# Power_18.net
KiCad netlist of a schematic drawn in Altium Designer
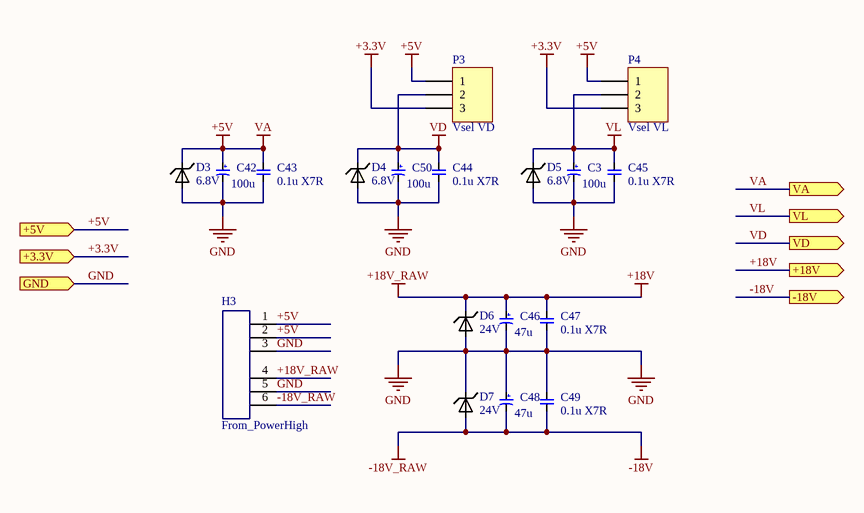
[diagram p0: Power_18.SchDoc]

(export (version "E")
  (design (tool "Eeschema 10.0.6"))
  (components
    (comp (ref "C3")
      (value "100u")
      (footprint "cap 4x5.4")
      (libsource (lib "Codec_board") (part "Cap_electrolytic"))
    )
    (comp (ref "C42")
      (value "100u")
      (footprint "cap 4x5.4")
      (libsource (lib "Codec_board") (part "Cap_electrolytic"))
    )
    (comp (ref "C43") (value "0.1u X7R") (footprint "0805_cap") (libsource (lib "Codec_board") (part "Cap")))
    (comp (ref "C44") (value "0.1u X7R") (footprint "0805_cap") (libsource (lib "Codec_board") (part "Cap")))
    (comp (ref "C45") (value "0.1u X7R") (footprint "0805_cap") (libsource (lib "Codec_board") (part "Cap")))
    (comp (ref "C46")
      (value "47u")
      (footprint "cap 4x5.4")
      (libsource (lib "Codec_board") (part "Cap_electrolytic"))
    )
    (comp (ref "C47") (value "0.1u X7R") (footprint "0805_cap") (libsource (lib "Codec_board") (part "Cap")))
    (comp (ref "C48")
      (value "47u")
      (footprint "cap 4x5.4")
      (libsource (lib "Codec_board") (part "Cap_electrolytic"))
    )
    (comp (ref "C49") (value "0.1u X7R") (footprint "0805_cap") (libsource (lib "Codec_board") (part "Cap")))
    (comp (ref "C50")
      (value "100u")
      (footprint "cap 4x5.4")
      (libsource (lib "Codec_board") (part "Cap_electrolytic"))
    )
    (comp (ref "D3") (value "6.8V") (footprint "SOD-80") (libsource (lib "Codec_board") (part "Stabilitron")))
    (comp (ref "D4") (value "6.8V") (footprint "SOD-80") (libsource (lib "Codec_board") (part "Stabilitron")))
    (comp (ref "D5") (value "6.8V") (footprint "SOD-80") (libsource (lib "Codec_board") (part "Stabilitron")))
    (comp (ref "D6") (value "24V") (footprint "SOD-80") (libsource (lib "Codec_board") (part "Stabilitron")))
    (comp (ref "D7") (value "24V") (footprint "SOD-80") (libsource (lib "Codec_board") (part "Stabilitron")))
    (comp (ref "H3")
      (value "From_PowerHigh")
      (footprint "header-6_male")
      (libsource (lib "Codec_board") (part "arduino_header_6"))
    )
    (comp (ref "P3")
      (value "Vsel VD")
      (footprint "HDR1X3")
      (description "Header, 3-Pin")
      (fields (field (name "PUBLISHER") "Altium Limited"))
      (libsource (lib "Miscellaneous Connectors") (part "Header 3"))
    )
    (comp (ref "P4")
      (value "Vsel VL")
      (footprint "HDR1X3")
      (description "Header, 3-Pin")
      (fields (field (name "PUBLISHER") "Altium Limited"))
      (libsource (lib "Miscellaneous Connectors") (part "Header 3"))
    )
  )
  (nets
    (net (code "1") (name "+3.3V") (class "Default")
      (node (ref "P3") (pin "3") (pinfunction "3_3") (pintype "passive"))
      (node (ref "P4") (pin "3") (pinfunction "3_3") (pintype "passive"))
    )
    (net (code "2") (name "+5V") (class "Default")
      (node (ref "C42") (pin "1") (pinfunction "1_1") (pintype "passive"))
      (node (ref "C43") (pin "2") (pinfunction "2_2") (pintype "passive"))
      (node (ref "D3") (pin "C") (pinfunction "C_C") (pintype "passive"))
      (node (ref "H3") (pin "1") (pinfunction "1_1") (pintype "passive"))
      (node (ref "H3") (pin "2") (pinfunction "2_2") (pintype "passive"))
      (node (ref "P3") (pin "1") (pinfunction "1_1") (pintype "passive"))
      (node (ref "P4") (pin "1") (pinfunction "1_1") (pintype "passive"))
    )
    (net (code "3") (name "+18V") (class "Default")
      (node (ref "C46") (pin "1") (pinfunction "1_1") (pintype "passive"))
      (node (ref "C47") (pin "2") (pinfunction "2_2") (pintype "passive"))
      (node (ref "D6") (pin "C") (pinfunction "C_C") (pintype "passive"))
      (node (ref "H3") (pin "4") (pinfunction "4_4") (pintype "passive"))
    )
    (net (code "4") (name "-18V") (class "Default")
      (node (ref "C48") (pin "2") (pinfunction "2_2") (pintype "passive"))
      (node (ref "C49") (pin "1") (pinfunction "1_1") (pintype "passive"))
      (node (ref "D7") (pin "A") (pinfunction "A_A") (pintype "passive"))
      (node (ref "H3") (pin "6") (pinfunction "6_6") (pintype "passive"))
    )
    (net (code "5") (name "GND") (class "Default")
      (node (ref "C3") (pin "2") (pinfunction "2_2") (pintype "passive"))
      (node (ref "C42") (pin "2") (pinfunction "2_2") (pintype "passive"))
      (node (ref "C43") (pin "1") (pinfunction "1_1") (pintype "passive"))
      (node (ref "C44") (pin "1") (pinfunction "1_1") (pintype "passive"))
      (node (ref "C45") (pin "1") (pinfunction "1_1") (pintype "passive"))
      (node (ref "C46") (pin "2") (pinfunction "2_2") (pintype "passive"))
      (node (ref "C47") (pin "1") (pinfunction "1_1") (pintype "passive"))
      (node (ref "C48") (pin "1") (pinfunction "1_1") (pintype "passive"))
      (node (ref "C49") (pin "2") (pinfunction "2_2") (pintype "passive"))
      (node (ref "C50") (pin "2") (pinfunction "2_2") (pintype "passive"))
      (node (ref "D3") (pin "A") (pinfunction "A_A") (pintype "passive"))
      (node (ref "D4") (pin "A") (pinfunction "A_A") (pintype "passive"))
      (node (ref "D5") (pin "A") (pinfunction "A_A") (pintype "passive"))
      (node (ref "D6") (pin "A") (pinfunction "A_A") (pintype "passive"))
      (node (ref "D7") (pin "C") (pinfunction "C_C") (pintype "passive"))
      (node (ref "H3") (pin "3") (pinfunction "3_3") (pintype "passive"))
      (node (ref "H3") (pin "5") (pinfunction "5_5") (pintype "passive"))
    )
    (net (code "6") (name "VD") (class "Default")
      (node (ref "C44") (pin "2") (pinfunction "2_2") (pintype "passive"))
      (node (ref "C50") (pin "1") (pinfunction "1_1") (pintype "passive"))
      (node (ref "D4") (pin "C") (pinfunction "C_C") (pintype "passive"))
      (node (ref "P3") (pin "2") (pinfunction "2_2") (pintype "passive"))
    )
    (net (code "7") (name "VL") (class "Default")
      (node (ref "C3") (pin "1") (pinfunction "1_1") (pintype "passive"))
      (node (ref "C45") (pin "2") (pinfunction "2_2") (pintype "passive"))
      (node (ref "D5") (pin "C") (pinfunction "C_C") (pintype "passive"))
      (node (ref "P4") (pin "2") (pinfunction "2_2") (pintype "passive"))
    )
  )
)
